# mapleCUx_large_050.net
KiCad netlist of a schematic drawn in EAGLE
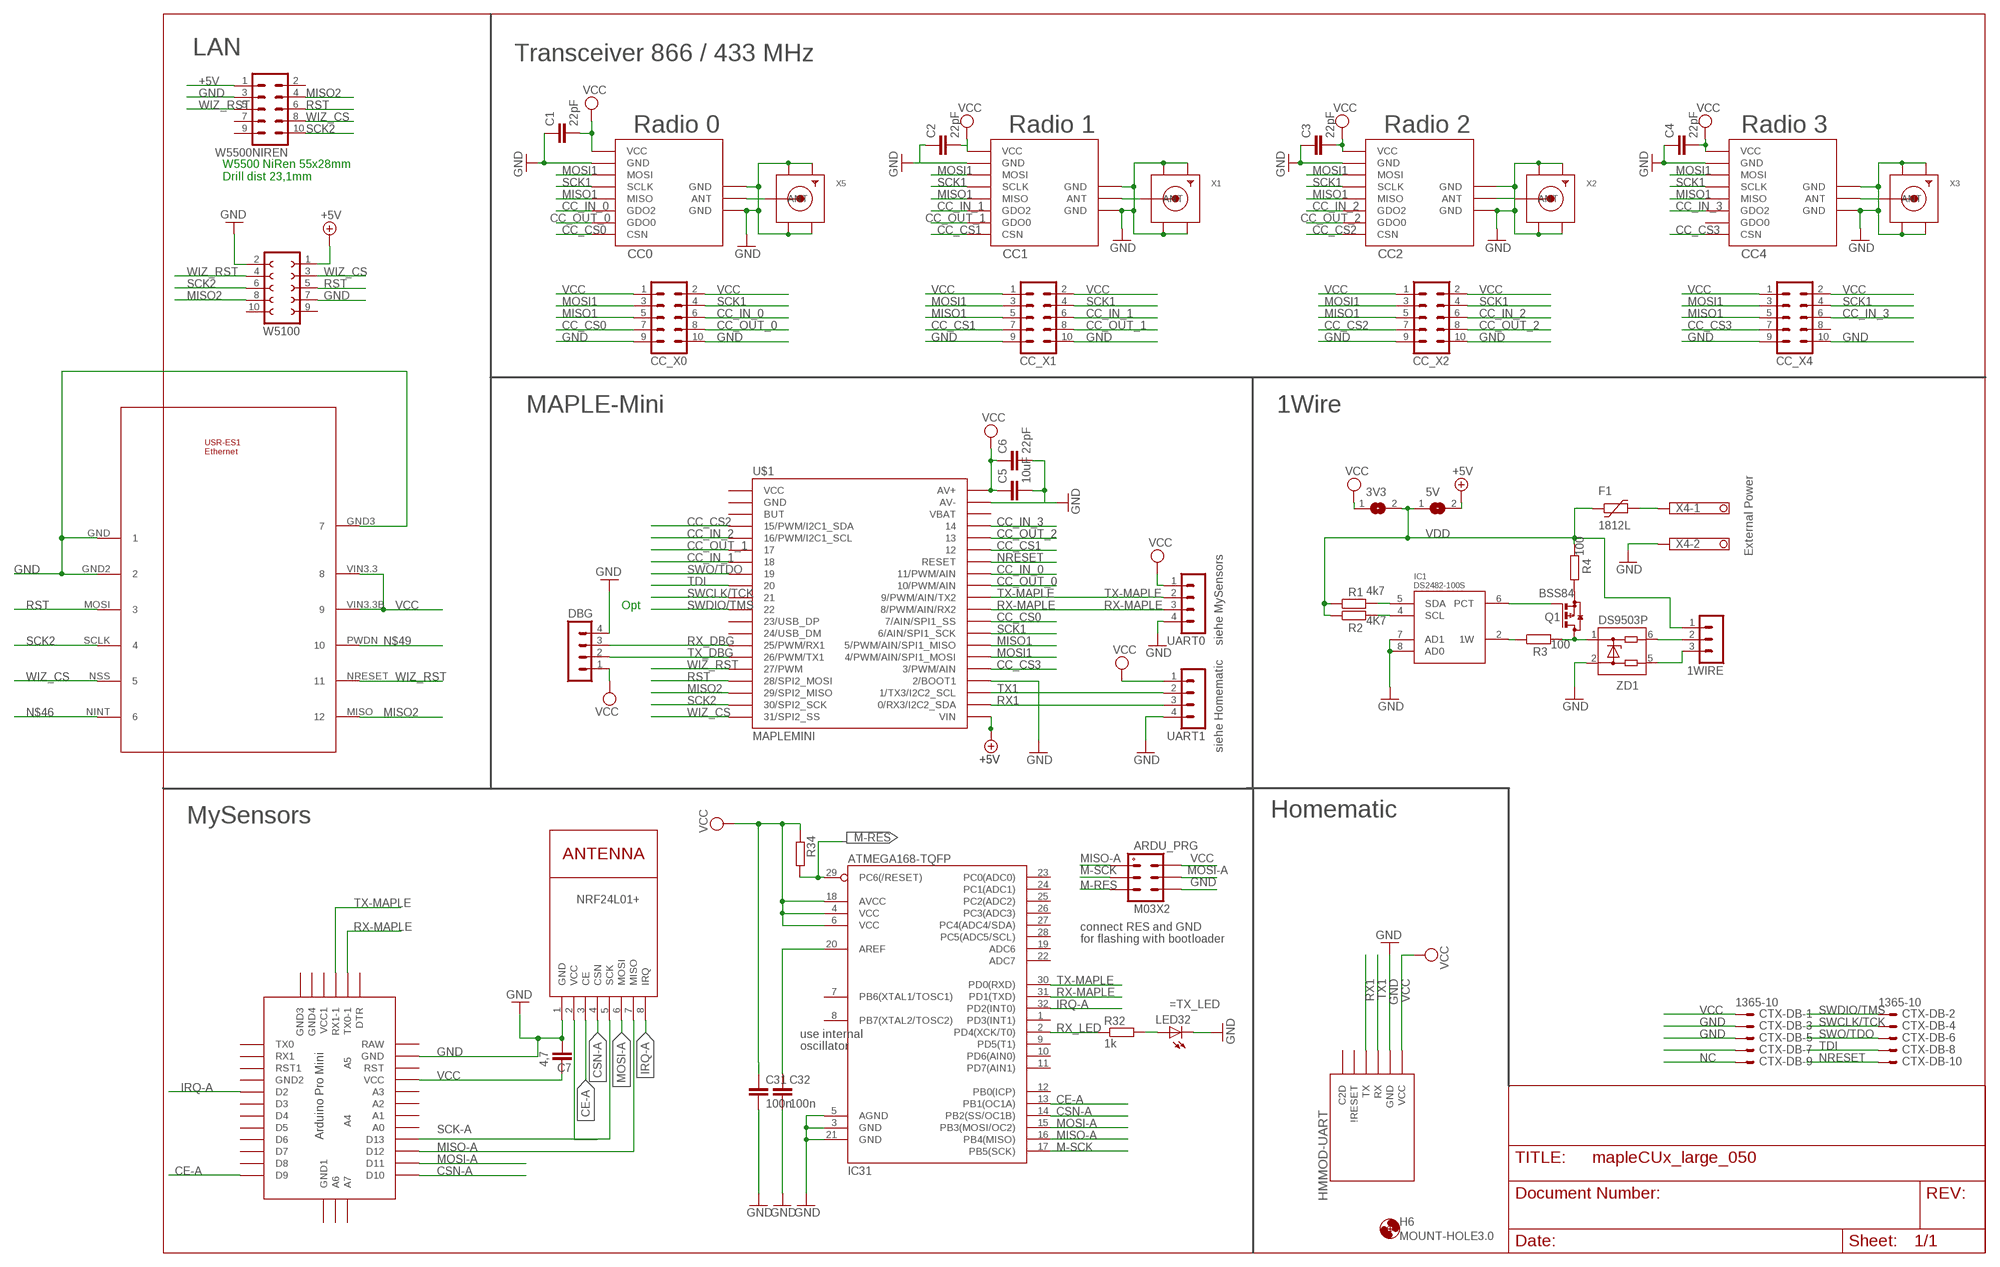
[diagram p0: schematic, sheet 1]

(export (version "E")
  (design (tool "Eeschema 10.0.6"))
  (components
    (comp (ref "1WIRE")
      (value "MA03-1")
      (footprint "eagle-import:MA03-1")
      (libsource (lib "eagle-import") (part "MA03-1"))
    )
    (comp (ref "3V3") (value "SJ") (footprint "eagle-import:SJ") (libsource (lib "eagle-import") (part "SJ")))
    (comp (ref "5V") (value "SJ") (footprint "eagle-import:SJ") (libsource (lib "eagle-import") (part "SJ")))
    (comp (ref "ARDU_PRG")
      (value "M03X2")
      (footprint "eagle-import:2X03-1.27MM_SMD")
      (libsource (lib "eagle-import") (part "M03X2"))
    )
    (comp (ref "C1")
      (value "22pF")
      (footprint "eagle-import:C0805")
      (libsource (lib "eagle-import") (part "C-EUC0805"))
    )
    (comp (ref "C2")
      (value "22pF")
      (footprint "eagle-import:C0805")
      (libsource (lib "eagle-import") (part "C-EUC0805"))
    )
    (comp (ref "C3")
      (value "22pF")
      (footprint "eagle-import:C0805")
      (libsource (lib "eagle-import") (part "C-EUC0805"))
    )
    (comp (ref "C4")
      (value "22pF")
      (footprint "eagle-import:C0805")
      (libsource (lib "eagle-import") (part "C-EUC0805"))
    )
    (comp (ref "C5")
      (value "10uF")
      (footprint "eagle-import:C1210")
      (libsource (lib "eagle-import") (part "C-EUC1210"))
    )
    (comp (ref "C6")
      (value "22pF")
      (footprint "eagle-import:C0805")
      (libsource (lib "eagle-import") (part "C-EUC0805"))
    )
    (comp (ref "C7")
      (value "4,7")
      (footprint "eagle-import:C1210")
      (libsource (lib "eagle-import") (part "C-EUC1210"))
    )
    (comp (ref "C31")
      (value "100n")
      (footprint "eagle-import:C0805")
      (libsource (lib "eagle-import") (part "C-EUC0805"))
    )
    (comp (ref "C32")
      (value "100n")
      (footprint "eagle-import:C0805")
      (libsource (lib "eagle-import") (part "C-EUC0805"))
    )
    (comp (ref "CC0")
      (value "CC1101_MODULE1SMD")
      (footprint "eagle-import:CC1101_MODULE1_SMD")
      (libsource (lib "eagle-import") (part "CC1101_MODULE1SMD"))
    )
    (comp (ref "CC1")
      (value "CC1101_MODULE1SMD")
      (footprint "eagle-import:CC1101_MODULE1_SMD")
      (libsource (lib "eagle-import") (part "CC1101_MODULE1SMD"))
    )
    (comp (ref "CC2")
      (value "CC1101_MODULE1SMD")
      (footprint "eagle-import:CC1101_MODULE1_SMD")
      (libsource (lib "eagle-import") (part "CC1101_MODULE1SMD"))
    )
    (comp (ref "CC4")
      (value "CC1101_MODULE1SMD")
      (footprint "eagle-import:CC1101_MODULE1_SMD")
      (libsource (lib "eagle-import") (part "CC1101_MODULE1SMD"))
    )
    (comp (ref "CC_X0")
      (value "MA05-2")
      (footprint "eagle-import:MA05-2")
      (libsource (lib "eagle-import") (part "MA05-2"))
    )
    (comp (ref "CC_X1")
      (value "MA05-2")
      (footprint "eagle-import:MA05-2")
      (libsource (lib "eagle-import") (part "MA05-2"))
    )
    (comp (ref "CC_X2")
      (value "MA05-2")
      (footprint "eagle-import:MA05-2")
      (libsource (lib "eagle-import") (part "MA05-2"))
    )
    (comp (ref "CC_X4")
      (value "MA05-2")
      (footprint "eagle-import:MA05-2")
      (libsource (lib "eagle-import") (part "MA05-2"))
    )
    (comp (ref "CTX-DB")
      (value "1365-10")
      (footprint "eagle-import:1365-10")
      (libsource (lib "eagle-import") (part "1365-10"))
    )
    (comp (ref "DBG")
      (value "MA04-1")
      (footprint "eagle-import:MA04-1")
      (libsource (lib "eagle-import") (part "MA04-1"))
    )
    (comp (ref "F1")
      (value "1812L")
      (footprint "eagle-import:1812L")
      (libsource (lib "eagle-import") (part "1812L"))
    )
    (comp (ref "H6")
      (value "MOUNT-HOLE3.0")
      (footprint "eagle-import:3,0")
      (libsource (lib "eagle-import") (part "MOUNT-HOLE3.0"))
    )
    (comp (ref "HMMOD-UART")
      (value "HM-MOD-UARTDIL")
      (footprint "eagle-import:HM-MOD-UART-DIL")
      (libsource (lib "eagle-import") (part "HM-MOD-UARTDIL"))
    )
    (comp (ref "IC1")
      (value "DS2482-100S")
      (footprint "eagle-import:SO08")
      (libsource (lib "eagle-import") (part "DS2482-100S"))
    )
    (comp (ref "IC31")
      (value "ATMEGA168-TQFP")
      (footprint "eagle-import:TQFP32-08")
      (libsource (lib "eagle-import") (part "ATMEGA168-TQFP"))
    )
    (comp (ref "LED32")
      (value "LEDCHIPLED_0805")
      (footprint "eagle-import:CHIPLED_0805")
      (libsource (lib "eagle-import") (part "LEDCHIPLED_0805"))
    )
    (comp (ref "NRF24L01+")
      (value "NRF24L01+")
      (footprint "eagle-import:WIRELESS-NRF24L01")
      (libsource (lib "eagle-import") (part "WIRELESS-NRF24L01"))
    )
    (comp (ref "Q1")
      (value "BSS84")
      (footprint "eagle-import:SOT23")
      (libsource (lib "eagle-import") (part "BSS84"))
    )
    (comp (ref "R1")
      (value "4k7")
      (footprint "eagle-import:R0805")
      (libsource (lib "eagle-import") (part "R-EU_R0805"))
    )
    (comp (ref "R2")
      (value "4K7")
      (footprint "eagle-import:R0805")
      (libsource (lib "eagle-import") (part "R-EU_R0805"))
    )
    (comp (ref "R3")
      (value "100")
      (footprint "eagle-import:R0805")
      (libsource (lib "eagle-import") (part "R-EU_R0805"))
    )
    (comp (ref "R4")
      (value "100")
      (footprint "eagle-import:R0805")
      (libsource (lib "eagle-import") (part "R-EU_R0805"))
    )
    (comp (ref "R32")
      (value "1k")
      (footprint "eagle-import:R0805")
      (libsource (lib "eagle-import") (part "R-EU_R0805"))
    )
    (comp (ref "R34")
      (value "R-EU_R0805")
      (footprint "eagle-import:R0805")
      (libsource (lib "eagle-import") (part "R-EU_R0805"))
    )
    (comp (ref "U$1")
      (value "MAPLEMINI")
      (footprint "eagle-import:20-DIP")
      (libsource (lib "eagle-import") (part "MAPLEMINI"))
    )
    (comp (ref "U$2")
      (value "ABK-PRO-MINI")
      (footprint "eagle-import:ABK-PRO-MINI")
      (libsource (lib "eagle-import") (part "ABK-PRO-MINI"))
    )
    (comp (ref "U$3")
      (value "USR-ES1")
      (footprint "eagle-import:USR-ES1")
      (libsource (lib "eagle-import") (part "USR-ES1"))
    )
    (comp (ref "UART0")
      (value "MA04-1")
      (footprint "eagle-import:MA04-1")
      (libsource (lib "eagle-import") (part "MA04-1"))
    )
    (comp (ref "UART1")
      (value "MA04-1")
      (footprint "eagle-import:MA04-1")
      (libsource (lib "eagle-import") (part "MA04-1"))
    )
    (comp (ref "W5100")
      (value "FE05-2")
      (footprint "eagle-import:FE05-2")
      (libsource (lib "eagle-import") (part "FE05-2"))
    )
    (comp (ref "W5500NIREN")
      (value "MA05-2")
      (footprint "eagle-import:MA05-2")
      (libsource (lib "eagle-import") (part "MA05-2"))
    )
    (comp (ref "X1")
      (value "SMACONNECTOR_EDGE_UFL")
      (footprint "eagle-import:SMA_EDGELAUNCH_UFL")
      (libsource (lib "eagle-import") (part "SMACONNECTOR_EDGE_UFL"))
    )
    (comp (ref "X2")
      (value "SMACONNECTOR_EDGE_UFL")
      (footprint "eagle-import:SMA_EDGELAUNCH_UFL")
      (libsource (lib "eagle-import") (part "SMACONNECTOR_EDGE_UFL"))
    )
    (comp (ref "X3")
      (value "SMACONNECTOR_EDGE_UFL")
      (footprint "eagle-import:SMA_EDGELAUNCH_UFL")
      (libsource (lib "eagle-import") (part "SMACONNECTOR_EDGE_UFL"))
    )
    (comp (ref "X4")
      (value "1751248")
      (footprint "eagle-import:1751248")
      (libsource (lib "eagle-import") (part "1751248"))
    )
    (comp (ref "X5")
      (value "SMACONNECTOR_EDGE_UFL")
      (footprint "eagle-import:SMA_EDGELAUNCH_UFL")
      (libsource (lib "eagle-import") (part "SMACONNECTOR_EDGE_UFL"))
    )
    (comp (ref "ZD1")
      (value "DS9503P")
      (footprint "eagle-import:TSOC6")
      (libsource (lib "eagle-import") (part "DS9503P"))
    )
  )
  (nets
    (net (code "1") (name "+5V") (class "Default")
      (node (ref "5V") (pin "2") (pinfunction "2_2") (pintype "passive"))
      (node (ref "U$1") (pin "21") (pinfunction "VIN_21") (pintype "bidirectional"))
      (node (ref "W5100") (pin "1") (pinfunction "1_1") (pintype "passive"))
      (node (ref "W5500NIREN") (pin "1") (pinfunction "1_1") (pintype "passive"))
    )
    (net (code "2") (name "/CC_CS0") (class "Default")
      (node (ref "CC0") (pin "CSN") (pinfunction "CSN_CSN") (pintype "bidirectional"))
      (node (ref "CC_X0") (pin "7") (pinfunction "7_7") (pintype "passive"))
      (node (ref "U$1") (pin "29") (pinfunction "7/AIN/SPI1_SS_29") (pintype "bidirectional"))
    )
    (net (code "3") (name "/CC_CS1") (class "Default")
      (node (ref "CC1") (pin "CSN") (pinfunction "CSN_CSN") (pintype "bidirectional"))
      (node (ref "CC_X1") (pin "7") (pinfunction "7_7") (pintype "passive"))
      (node (ref "U$1") (pin "35") (pinfunction "12_35") (pintype "bidirectional"))
    )
    (net (code "4") (name "/CC_CS2") (class "Default")
      (node (ref "CC2") (pin "CSN") (pinfunction "CSN_CSN") (pintype "bidirectional"))
      (node (ref "CC_X2") (pin "7") (pinfunction "7_7") (pintype "passive"))
      (node (ref "U$1") (pin "4") (pinfunction "15/PWM/I2C1_SDA_4") (pintype "bidirectional"))
    )
    (net (code "5") (name "/CC_CS3") (class "Default")
      (node (ref "CC4") (pin "CSN") (pinfunction "CSN_CSN") (pintype "bidirectional"))
      (node (ref "CC_X4") (pin "7") (pinfunction "7_7") (pintype "passive"))
      (node (ref "U$1") (pin "25") (pinfunction "3/PWM/AIN_25") (pintype "bidirectional"))
    )
    (net (code "6") (name "/CC_IN_0") (class "Default")
      (node (ref "CC0") (pin "GDO2") (pinfunction "GDO2_GDO2") (pintype "bidirectional"))
      (node (ref "CC_X0") (pin "6") (pinfunction "6_6") (pintype "passive"))
      (node (ref "U$1") (pin "33") (pinfunction "11/PWM/AIN_33") (pintype "bidirectional"))
    )
    (net (code "7") (name "/CC_IN_1") (class "Default")
      (node (ref "CC1") (pin "GDO2") (pinfunction "GDO2_GDO2") (pintype "bidirectional"))
      (node (ref "CC_X1") (pin "6") (pinfunction "6_6") (pintype "passive"))
      (node (ref "U$1") (pin "7") (pinfunction "18_7") (pintype "bidirectional"))
    )
    (net (code "8") (name "/CC_IN_2") (class "Default")
      (node (ref "CC2") (pin "GDO2") (pinfunction "GDO2_GDO2") (pintype "bidirectional"))
      (node (ref "CC_X2") (pin "6") (pinfunction "6_6") (pintype "passive"))
      (node (ref "U$1") (pin "5") (pinfunction "16/PWM/I2C1_SCL_5") (pintype "bidirectional"))
    )
    (net (code "9") (name "/CC_IN_3") (class "Default")
      (node (ref "CC4") (pin "GDO2") (pinfunction "GDO2_GDO2") (pintype "bidirectional"))
      (node (ref "CC_X4") (pin "6") (pinfunction "6_6") (pintype "passive"))
      (node (ref "U$1") (pin "37") (pinfunction "14_37") (pintype "bidirectional"))
    )
    (net (code "10") (name "/CC_OUT_0") (class "Default")
      (node (ref "CC0") (pin "GDO0") (pinfunction "GDO0_GDO0") (pintype "bidirectional"))
      (node (ref "CC_X0") (pin "8") (pinfunction "8_8") (pintype "passive"))
      (node (ref "U$1") (pin "32") (pinfunction "10/PWM/AIN_32") (pintype "bidirectional"))
    )
    (net (code "11") (name "/CC_OUT_1") (class "Default")
      (node (ref "CC1") (pin "GDO0") (pinfunction "GDO0_GDO0") (pintype "bidirectional"))
      (node (ref "CC_X1") (pin "8") (pinfunction "8_8") (pintype "passive"))
      (node (ref "U$1") (pin "6") (pinfunction "17_6") (pintype "bidirectional"))
    )
    (net (code "12") (name "/CC_OUT_2") (class "Default")
      (node (ref "CC2") (pin "GDO0") (pinfunction "GDO0_GDO0") (pintype "bidirectional"))
      (node (ref "CC_X2") (pin "8") (pinfunction "8_8") (pintype "passive"))
      (node (ref "U$1") (pin "36") (pinfunction "13_36") (pintype "bidirectional"))
    )
    (net (code "13") (name "/M-RES") (class "Default")
      (node (ref "ARDU_PRG") (pin "P$5") (pinfunction "5_P$5") (pintype "passive"))
      (node (ref "IC31") (pin "29") (pinfunction "PC6(/RESET)_29") (pintype "bidirectional"))
      (node (ref "R34") (pin "2") (pinfunction "2_2") (pintype "passive"))
    )
    (net (code "14") (name "/M-SCK") (class "Default")
      (node (ref "ARDU_PRG") (pin "P$3") (pinfunction "3_P$3") (pintype "passive"))
      (node (ref "IC31") (pin "17") (pinfunction "PB5(SCK)_17") (pintype "bidirectional"))
    )
    (net (code "15") (name "/MISO-A") (class "Default")
      (node (ref "ARDU_PRG") (pin "P$1") (pinfunction "1_P$1") (pintype "passive"))
      (node (ref "IC31") (pin "16") (pinfunction "PB4(MISO)_16") (pintype "bidirectional"))
      (node (ref "NRF24L01+") (pin "7") (pinfunction "MISO_7") (pintype "bidirectional"))
      (node (ref "U$2") (pin "D12") (pinfunction "D12_D12") (pintype "bidirectional"))
    )
    (net (code "16") (name "/MISO1") (class "Default")
      (node (ref "CC0") (pin "MISO") (pinfunction "MISO_MISO") (pintype "bidirectional"))
      (node (ref "CC1") (pin "MISO") (pinfunction "MISO_MISO") (pintype "bidirectional"))
      (node (ref "CC2") (pin "MISO") (pinfunction "MISO_MISO") (pintype "bidirectional"))
      (node (ref "CC4") (pin "MISO") (pinfunction "MISO_MISO") (pintype "bidirectional"))
      (node (ref "CC_X0") (pin "5") (pinfunction "5_5") (pintype "passive"))
      (node (ref "CC_X1") (pin "5") (pinfunction "5_5") (pintype "passive"))
      (node (ref "CC_X2") (pin "5") (pinfunction "5_5") (pintype "passive"))
      (node (ref "CC_X4") (pin "5") (pinfunction "5_5") (pintype "passive"))
      (node (ref "U$1") (pin "27") (pinfunction "5/PWM/AIN/SPI1_MISO_27") (pintype "bidirectional"))
    )
    (net (code "17") (name "/MISO2") (class "Default")
      (node (ref "U$1") (pin "18") (pinfunction "29/SPI2_MISO_18") (pintype "bidirectional"))
      (node (ref "U$3") (pin "MISO") (pinfunction "12_MISO") (pintype "bidirectional"))
      (node (ref "W5100") (pin "8") (pinfunction "8_8") (pintype "passive"))
      (node (ref "W5500NIREN") (pin "4") (pinfunction "4_4") (pintype "passive"))
    )
    (net (code "18") (name "/MOSI1") (class "Default")
      (node (ref "CC0") (pin "MOSI") (pinfunction "MOSI_MOSI") (pintype "bidirectional"))
      (node (ref "CC1") (pin "MOSI") (pinfunction "MOSI_MOSI") (pintype "bidirectional"))
      (node (ref "CC2") (pin "MOSI") (pinfunction "MOSI_MOSI") (pintype "bidirectional"))
      (node (ref "CC4") (pin "MOSI") (pinfunction "MOSI_MOSI") (pintype "bidirectional"))
      (node (ref "CC_X0") (pin "3") (pinfunction "3_3") (pintype "passive"))
      (node (ref "CC_X1") (pin "3") (pinfunction "3_3") (pintype "passive"))
      (node (ref "CC_X2") (pin "3") (pinfunction "3_3") (pintype "passive"))
      (node (ref "CC_X4") (pin "3") (pinfunction "3_3") (pintype "passive"))
      (node (ref "U$1") (pin "26") (pinfunction "4/PWM/AIN/SPI1_MOSI_26") (pintype "bidirectional"))
    )
    (net (code "19") (name "/N$46") (class "Default")
      (node (ref "U$3") (pin "NINT") (pinfunction "6_NINT") (pintype "bidirectional"))
    )
    (net (code "20") (name "/N$49") (class "Default")
      (node (ref "U$3") (pin "PWDN") (pinfunction "10_PWDN") (pintype "bidirectional"))
    )
    (net (code "21") (name "/NC") (class "Default")
      (node (ref "CTX-DB") (pin "9") (pinfunction "S_9") (pintype "passive"))
    )
    (net (code "22") (name "/NRESET") (class "Default")
      (node (ref "CTX-DB") (pin "10") (pinfunction "S_10") (pintype "passive"))
      (node (ref "U$1") (pin "34") (pinfunction "RESET_34") (pintype "bidirectional"))
    )
    (net (code "23") (name "/RST") (class "Default")
      (node (ref "U$1") (pin "17") (pinfunction "28/SPI2_MOSI_17") (pintype "bidirectional"))
      (node (ref "U$3") (pin "MOSI") (pinfunction "3_MOSI") (pintype "bidirectional"))
      (node (ref "W5100") (pin "5") (pinfunction "5_5") (pintype "passive"))
      (node (ref "W5500NIREN") (pin "6") (pinfunction "6_6") (pintype "passive"))
    )
    (net (code "24") (name "/RX-MAPLE") (class "Default")
      (node (ref "IC31") (pin "31") (pinfunction "PD1(TXD)_31") (pintype "bidirectional"))
      (node (ref "U$1") (pin "30") (pinfunction "8/PWM/AIN/RX2_30") (pintype "bidirectional"))
      (node (ref "U$2") (pin "TX0-1") (pinfunction "TX0-1_TX0-1") (pintype "bidirectional"))
      (node (ref "UART0") (pin "3") (pinfunction "3_3") (pintype "passive"))
    )
    (net (code "25") (name "/RX1") (class "Default")
      (node (ref "HMMOD-UART") (pin "5") (pinfunction "TX_5") (pintype "bidirectional"))
      (node (ref "U$1") (pin "22") (pinfunction "0/RX3/I2C2_SDA_22") (pintype "bidirectional"))
      (node (ref "UART1") (pin "3") (pinfunction "3_3") (pintype "passive"))
    )
    (net (code "26") (name "/RX_DBG") (class "Default")
      (node (ref "DBG") (pin "3") (pinfunction "3_3") (pintype "passive"))
      (node (ref "U$1") (pin "14") (pinfunction "25/PWM/RX1_14") (pintype "bidirectional"))
    )
    (net (code "27") (name "/RX_LED") (class "Default")
      (node (ref "IC31") (pin "2") (pinfunction "PD4(XCK/T0)_2") (pintype "bidirectional"))
      (node (ref "R32") (pin "1") (pinfunction "1_1") (pintype "passive"))
    )
    (net (code "28") (name "/SCK-A") (class "Default")
      (node (ref "NRF24L01+") (pin "5") (pinfunction "SCK_5") (pintype "bidirectional"))
      (node (ref "U$2") (pin "D13") (pinfunction "D13_D13") (pintype "bidirectional"))
    )
    (net (code "29") (name "/SCK1") (class "Default")
      (node (ref "CC0") (pin "SCLK") (pinfunction "SCLK_SCLK") (pintype "bidirectional"))
      (node (ref "CC1") (pin "SCLK") (pinfunction "SCLK_SCLK") (pintype "bidirectional"))
      (node (ref "CC2") (pin "SCLK") (pinfunction "SCLK_SCLK") (pintype "bidirectional"))
      (node (ref "CC4") (pin "SCLK") (pinfunction "SCLK_SCLK") (pintype "bidirectional"))
      (node (ref "CC_X0") (pin "4") (pinfunction "4_4") (pintype "passive"))
      (node (ref "CC_X1") (pin "4") (pinfunction "4_4") (pintype "passive"))
      (node (ref "CC_X2") (pin "4") (pinfunction "4_4") (pintype "passive"))
      (node (ref "CC_X4") (pin "4") (pinfunction "4_4") (pintype "passive"))
      (node (ref "U$1") (pin "28") (pinfunction "6/AIN/SPI1_SCK_28") (pintype "bidirectional"))
    )
    (net (code "30") (name "/SCK2") (class "Default")
      (node (ref "U$1") (pin "19") (pinfunction "30/SPI2_SCK_19") (pintype "bidirectional"))
      (node (ref "U$3") (pin "SCLK") (pinfunction "4_SCLK") (pintype "bidirectional"))
      (node (ref "W5100") (pin "6") (pinfunction "6_6") (pintype "passive"))
      (node (ref "W5500NIREN") (pin "10") (pinfunction "10_10") (pintype "passive"))
    )
    (net (code "31") (name "/SWCLK{slash}TCK") (class "Default")
      (node (ref "CTX-DB") (pin "4") (pinfunction "S_4") (pintype "passive"))
      (node (ref "U$1") (pin "10") (pinfunction "21_10") (pintype "bidirectional"))
    )
    (net (code "32") (name "/SWDIO{slash}TMS") (class "Default")
      (node (ref "CTX-DB") (pin "2") (pinfunction "S_2") (pintype "passive"))
      (node (ref "U$1") (pin "11") (pinfunction "22_11") (pintype "bidirectional"))
    )
    (net (code "33") (name "/SWO{slash}TDO") (class "Default")
      (node (ref "CTX-DB") (pin "6") (pinfunction "S_6") (pintype "passive"))
      (node (ref "U$1") (pin "8") (pinfunction "19_8") (pintype "bidirectional"))
    )
    (net (code "34") (name "/TDI") (class "Default")
      (node (ref "CTX-DB") (pin "8") (pinfunction "S_8") (pintype "passive"))
      (node (ref "U$1") (pin "9") (pinfunction "20_9") (pintype "bidirectional"))
    )
    (net (code "35") (name "/TX-MAPLE") (class "Default")
      (node (ref "IC31") (pin "30") (pinfunction "PD0(RXD)_30") (pintype "bidirectional"))
      (node (ref "U$1") (pin "31") (pinfunction "9/PWM/AIN/TX2_31") (pintype "bidirectional"))
      (node (ref "U$2") (pin "RX1-1") (pinfunction "RX1-1_RX1-1") (pintype "bidirectional"))
      (node (ref "UART0") (pin "2") (pinfunction "2_2") (pintype "passive"))
    )
    (net (code "36") (name "/TX1") (class "Default")
      (node (ref "HMMOD-UART") (pin "6") (pinfunction "RX_6") (pintype "bidirectional"))
      (node (ref "U$1") (pin "23") (pinfunction "1/TX3/I2C2_SCL_23") (pintype "bidirectional"))
      (node (ref "UART1") (pin "2") (pinfunction "2_2") (pintype "passive"))
    )
    (net (code "37") (name "/TX_DBG") (class "Default")
      (node (ref "DBG") (pin "2") (pinfunction "2_2") (pintype "passive"))
      (node (ref "U$1") (pin "15") (pinfunction "26/PWM/TX1_15") (pintype "bidirectional"))
    )
    (net (code "38") (name "/VDD") (class "Default")
      (node (ref "1WIRE") (pin "1") (pinfunction "1_1") (pintype "passive"))
      (node (ref "3V3") (pin "2") (pinfunction "2_2") (pintype "passive"))
      (node (ref "5V") (pin "1") (pinfunction "1_1") (pintype "passive"))
      (node (ref "F1") (pin "P$1") (pinfunction "1_P$1") (pintype "passive"))
      (node (ref "R1") (pin "1") (pinfunction "1_1") (pintype "passive"))
      (node (ref "R2") (pin "1") (pinfunction "1_1") (pintype "passive"))
      (node (ref "R4") (pin "2") (pinfunction "2_2") (pintype "passive"))
    )
    (net (code "39") (name "/WIZ_CS") (class "Default")
      (node (ref "U$1") (pin "20") (pinfunction "31/SPI2_SS_20") (pintype "bidirectional"))
      (node (ref "U$3") (pin "NSS") (pinfunction "5_NSS") (pintype "bidirectional"))
      (node (ref "W5100") (pin "3") (pinfunction "3_3") (pintype "passive"))
      (node (ref "W5500NIREN") (pin "8") (pinfunction "8_8") (pintype "passive"))
    )
    (net (code "40") (name "/WIZ_RST") (class "Default")
      (node (ref "U$1") (pin "16") (pinfunction "27/PWM_16") (pintype "bidirectional"))
      (node (ref "U$3") (pin "NRESET") (pinfunction "11_NRESET") (pintype "bidirectional"))
      (node (ref "W5100") (pin "4") (pinfunction "4_4") (pintype "passive"))
      (node (ref "W5500NIREN") (pin "5") (pinfunction "5_5") (pintype "passive"))
    )
    (net (code "41") (name "CE-A") (class "Default")
      (node (ref "IC31") (pin "13") (pinfunction "PB1(OC1A)_13") (pintype "bidirectional"))
      (node (ref "NRF24L01+") (pin "3") (pinfunction "CE_3") (pintype "bidirectional"))
      (node (ref "U$2") (pin "D9") (pinfunction "D9_D9") (pintype "bidirectional"))
    )
    (net (code "42") (name "CSN-A") (class "Default")
      (node (ref "IC31") (pin "14") (pinfunction "PB2(SS/OC1B)_14") (pintype "bidirectional"))
      (node (ref "NRF24L01+") (pin "4") (pinfunction "CSN_4") (pintype "bidirectional"))
      (node (ref "U$2") (pin "D10") (pinfunction "D10_D10") (pintype "bidirectional"))
    )
    (net (code "43") (name "GND") (class "Default")
      (node (ref "ARDU_PRG") (pin "P$6") (pinfunction "6_P$6") (pintype "passive"))
      (node (ref "C1") (pin "1") (pinfunction "1_1") (pintype "passive"))
      (node (ref "C2") (pin "1") (pinfunction "1_1") (pintype "passive"))
      (node (ref "C3") (pin "1") (pinfunction "1_1") (pintype "passive"))
      (node (ref "C31") (pin "2") (pinfunction "2_2") (pintype "passive"))
      (node (ref "C32") (pin "2") (pinfunction "2_2") (pintype "passive"))
      (node (ref "C4") (pin "1") (pinfunction "1_1") (pintype "passive"))
      (node (ref "C5") (pin "2") (pinfunction "2_2") (pintype "passive"))
      (node (ref "C6") (pin "2") (pinfunction "2_2") (pintype "passive"))
      (node (ref "C7") (pin "1") (pinfunction "1_1") (pintype "passive"))
      (node (ref "CC0") (pin "GND@0") (pinfunction "GND_GND@0") (pintype "power_in"))
      (node (ref "CC0") (pin "GND@1") (pinfunction "GND_GND@1") (pintype "power_in"))
      (node (ref "CC0") (pin "GND@2") (pinfunction "GND_GND@2") (pintype "power_in"))
      (node (ref "CC1") (pin "GND@0") (pinfunction "GND_GND@0") (pintype "power_in"))
      (node (ref "CC1") (pin "GND@1") (pinfunction "GND_GND@1") (pintype "power_in"))
      (node (ref "CC1") (pin "GND@2") (pinfunction "GND_GND@2") (pintype "power_in"))
      (node (ref "CC2") (pin "GND@0") (pinfunction "GND_GND@0") (pintype "power_in"))
      (node (ref "CC2") (pin "GND@1") (pinfunction "GND_GND@1") (pintype "power_in"))
      (node (ref "CC2") (pin "GND@2") (pinfunction "GND_GND@2") (pintype "power_in"))
      (node (ref "CC4") (pin "GND@0") (pinfunction "GND_GND@0") (pintype "power_in"))
      (node (ref "CC4") (pin "GND@1") (pinfunction "GND_GND@1") (pintype "power_in"))
      (node (ref "CC4") (pin "GND@2") (pinfunction "GND_GND@2") (pintype "power_in"))
      (node (ref "CC_X0") (pin "10") (pinfunction "10_10") (pintype "passive"))
      (node (ref "CC_X0") (pin "9") (pinfunction "9_9") (pintype "passive"))
      (node (ref "CC_X1") (pin "10") (pinfunction "10_10") (pintype "passive"))
      (node (ref "CC_X1") (pin "9") (pinfunction "9_9") (pintype "passive"))
      (node (ref "CC_X2") (pin "10") (pinfunction "10_10") (pintype "passive"))
      (node (ref "CC_X2") (pin "9") (pinfunction "9_9") (pintype "passive"))
      (node (ref "CC_X4") (pin "10") (pinfunction "10_10") (pintype "passive"))
      (node (ref "CC_X4") (pin "9") (pinfunction "9_9") (pintype "passive"))
      (node (ref "CTX-DB") (pin "3") (pinfunction "S_3") (pintype "passive"))
      (node (ref "CTX-DB") (pin "5") (pinfunction "S_5") (pintype "passive"))
      (node (ref "DBG") (pin "4") (pinfunction "4_4") (pintype "passive"))
      (node (ref "HMMOD-UART") (pin "2") (pinfunction "GND_2") (pintype "power_in"))
      (node (ref "IC1") (pin "7") (pinfunction "AD1_7") (pintype "input"))
      (node (ref "IC1") (pin "8") (pinfunction "AD0_8") (pintype "input"))
      (node (ref "IC31") (pin "21") (pinfunction "GND_21") (pintype "bidirectional"))
      (node (ref "IC31") (pin "3") (pinfunction "GND_3") (pintype "bidirectional"))
      (node (ref "IC31") (pin "5") (pinfunction "AGND_5") (pintype "bidirectional"))
      (node (ref "LED32") (pin "C") (pinfunction "C_C") (pintype "passive"))
      (node (ref "NRF24L01+") (pin "1") (pinfunction "GND_1") (pintype "power_in"))
      (node (ref "U$1") (pin "24") (pinfunction "2/BOOT1_24") (pintype "bidirectional"))
      (node (ref "U$1") (pin "39") (pinfunction "AV-_39") (pintype "bidirectional"))
      (node (ref "U$2") (pin "GND") (pinfunction "GND_GND") (pintype "bidirectional"))
      (node (ref "U$3") (pin "GND") (pinfunction "1_GND") (pintype "power_in"))
      (node (ref "U$3") (pin "GND2") (pinfunction "2_GND2") (pintype "power_in"))
      (node (ref "U$3") (pin "GND3") (pinfunction "7_GND3") (pintype "power_in"))
      (node (ref "UART0") (pin "4") (pinfunction "4_4") (pintype "passive"))
      (node (ref "UART1") (pin "4") (pinfunction "4_4") (pintype "passive"))
      (node (ref "W5100") (pin "2") (pinfunction "2_2") (pintype "passive"))
      (node (ref "W5100") (pin "7") (pinfunction "7_7") (pintype "passive"))
      (node (ref "W5500NIREN") (pin "3") (pinfunction "3_3") (pintype "passive"))
      (node (ref "X1") (pin "GND@1") (pinfunction "GND1_GND@1") (pintype "power_in"))
      (node (ref "X1") (pin "GND@2") (pinfunction "GND2_GND@2") (pintype "power_in"))
      (node (ref "X1") (pin "GND@3") (pinfunction "GND3_GND@3") (pintype "power_in"))
      (node (ref "X1") (pin "GND@4") (pinfunction "GND4_GND@4") (pintype "power_in"))
      (node (ref "X2") (pin "GND@1") (pinfunction "GND1_GND@1") (pintype "power_in"))
      (node (ref "X2") (pin "GND@2") (pinfunction "GND2_GND@2") (pintype "power_in"))
      (node (ref "X2") (pin "GND@3") (pinfunction "GND3_GND@3") (pintype "power_in"))
      (node (ref "X2") (pin "GND@4") (pinfunction "GND4_GND@4") (pintype "power_in"))
      (node (ref "X3") (pin "GND@1") (pinfunction "GND1_GND@1") (pintype "power_in"))
      (node (ref "X3") (pin "GND@2") (pinfunction "GND2_GND@2") (pintype "power_in"))
      (node (ref "X3") (pin "GND@3") (pinfunction "GND3_GND@3") (pintype "power_in"))
      (node (ref "X3") (pin "GND@4") (pinfunction "GND4_GND@4") (pintype "power_in"))
      (node (ref "X4") (pin "2") (pinfunction "K_2") (pintype "passive"))
      (node (ref "X5") (pin "GND@1") (pinfunction "GND1_GND@1") (pintype "power_in"))
      (node (ref "X5") (pin "GND@2") (pinfunction "GND2_GND@2") (pintype "power_in"))
      (node (ref "X5") (pin "GND@3") (pinfunction "GND3_GND@3") (pintype "power_in"))
      (node (ref "X5") (pin "GND@4") (pinfunction "GND4_GND@4") (pintype "power_in"))
      (node (ref "ZD1") (pin "2") (pinfunction "P$2_2") (pintype "passive"))
    )
    (net (code "44") (name "IRQ-A") (class "Default")
      (node (ref "IC31") (pin "32") (pinfunction "PD2(INT0)_32") (pintype "bidirectional"))
      (node (ref "NRF24L01+") (pin "8") (pinfunction "IRQ_8") (pintype "bidirectional"))
      (node (ref "U$2") (pin "D2") (pinfunction "D2_D2") (pintype "bidirectional"))
    )
    (net (code "45") (name "MOSI-A") (class "Default")
      (node (ref "ARDU_PRG") (pin "P$4") (pinfunction "4_P$4") (pintype "passive"))
      (node (ref "IC31") (pin "15") (pinfunction "PB3(MOSI/OC2)_15") (pintype "bidirectional"))
      (node (ref "NRF24L01+") (pin "6") (pinfunction "MOSI_6") (pintype "bidirectional"))
      (node (ref "U$2") (pin "D11") (pinfunction "D11_D11") (pintype "bidirectional"))
    )
    (net (code "46") (name "Net-(F1-2)") (class "Default")
      (node (ref "F1") (pin "P$2") (pinfunction "2_P$2") (pintype "passive"))
      (node (ref "X4") (pin "1") (pinfunction "K_1") (pintype "passive"))
    )
    (net (code "47") (name "Net-(IC1A-1W)") (class "Default")
      (node (ref "IC1") (pin "2") (pinfunction "1W_2") (pintype "open_collector"))
      (node (ref "R3") (pin "1") (pinfunction "1_1") (pintype "passive"))
    )
    (net (code "48") (name "Net-(IC1A-PCT)") (class "Default")
      (node (ref "IC1") (pin "6") (pinfunction "PCT_6") (pintype "output"))
      (node (ref "Q1") (pin "1") (pinfunction "G_1") (pintype "passive"))
    )
    (net (code "49") (name "Net-(IC1A-SCL)") (class "Default")
      (node (ref "IC1") (pin "4") (pinfunction "SCL_4") (pintype "input"))
      (node (ref "R2") (pin "2") (pinfunction "2_2") (pintype "passive"))
    )
    (net (code "50") (name "Net-(IC1A-SDA)") (class "Default")
      (node (ref "IC1") (pin "5") (pinfunction "SDA_5") (pintype "bidirectional"))
      (node (ref "R1") (pin "2") (pinfunction "2_2") (pintype "passive"))
    )
    (net (code "51") (name "Net-(IC31-AREF)") (class "Default")
      (node (ref "C32") (pin "1") (pinfunction "1_1") (pintype "passive"))
      (node (ref "IC31") (pin "20") (pinfunction "AREF_20") (pintype "bidirectional"))
    )
    (net (code "52") (name "Net-(LED32-PadA)") (class "Default")
      (node (ref "LED32") (pin "A") (pinfunction "A_A") (pintype "passive"))
      (node (ref "R32") (pin "2") (pinfunction "2_2") (pintype "passive"))
    )
    (net (code "53") (name "Net-(Q1-D)") (class "Default")
      (node (ref "Q1") (pin "3") (pinfunction "D_3") (pintype "passive"))
      (node (ref "R3") (pin "2") (pinfunction "2_2") (pintype "passive"))
      (node (ref "ZD1") (pin "1") (pinfunction "P$1_1") (pintype "passive"))
    )
    (net (code "54") (name "Net-(Q1-S)") (class "Default")
      (node (ref "Q1") (pin "2") (pinfunction "S_2") (pintype "passive"))
      (node (ref "R4") (pin "1") (pinfunction "1_1") (pintype "passive"))
    )
    (net (code "55") (name "Net-(X1-ANT)") (class "Default")
      (node (ref "CC1") (pin "ANT") (pinfunction "ANT_ANT") (pintype "output"))
      (node (ref "X1") (pin "P") (pinfunction "ANT_P") (pintype "bidirectional"))
    )
    (net (code "56") (name "Net-(X2-ANT)") (class "Default")
      (node (ref "CC2") (pin "ANT") (pinfunction "ANT_ANT") (pintype "output"))
      (node (ref "X2") (pin "P") (pinfunction "ANT_P") (pintype "bidirectional"))
    )
    (net (code "57") (name "Net-(X3-ANT)") (class "Default")
      (node (ref "CC4") (pin "ANT") (pinfunction "ANT_ANT") (pintype "output"))
      (node (ref "X3") (pin "P") (pinfunction "ANT_P") (pintype "bidirectional"))
    )
    (net (code "58") (name "Net-(X5-ANT)") (class "Default")
      (node (ref "CC0") (pin "ANT") (pinfunction "ANT_ANT") (pintype "output"))
      (node (ref "X5") (pin "P") (pinfunction "ANT_P") (pintype "bidirectional"))
    )
    (net (code "59") (name "Net-(ZD1-P$3)") (class "Default")
      (node (ref "1WIRE") (pin "3") (pinfunction "3_3") (pintype "passive"))
      (node (ref "ZD1") (pin "5") (pinfunction "P$3_5") (pintype "passive"))
    )
    (net (code "60") (name "Net-(ZD1-P$4)") (class "Default")
      (node (ref "1WIRE") (pin "2") (pinfunction "2_2") (pintype "passive"))
      (node (ref "ZD1") (pin "6") (pinfunction "P$4_6") (pintype "passive"))
    )
    (net (code "61") (name "VCC") (class "Default")
      (node (ref "3V3") (pin "1") (pinfunction "1_1") (pintype "passive"))
      (node (ref "ARDU_PRG") (pin "P$2") (pinfunction "2_P$2") (pintype "passive"))
      (node (ref "C1") (pin "2") (pinfunction "2_2") (pintype "passive"))
      (node (ref "C2") (pin "2") (pinfunction "2_2") (pintype "passive"))
      (node (ref "C3") (pin "2") (pinfunction "2_2") (pintype "passive"))
      (node (ref "C31") (pin "1") (pinfunction "1_1") (pintype "passive"))
      (node (ref "C4") (pin "2") (pinfunction "2_2") (pintype "passive"))
      (node (ref "C5") (pin "1") (pinfunction "1_1") (pintype "passive"))
      (node (ref "C6") (pin "1") (pinfunction "1_1") (pintype "passive"))
      (node (ref "C7") (pin "2") (pinfunction "2_2") (pintype "passive"))
      (node (ref "CC0") (pin "VCC") (pinfunction "VCC_VCC") (pintype "power_in"))
      (node (ref "CC1") (pin "VCC") (pinfunction "VCC_VCC") (pintype "power_in"))
      (node (ref "CC2") (pin "VCC") (pinfunction "VCC_VCC") (pintype "power_in"))
      (node (ref "CC4") (pin "VCC") (pinfunction "VCC_VCC") (pintype "power_in"))
      (node (ref "CC_X0") (pin "1") (pinfunction "1_1") (pintype "passive"))
      (node (ref "CC_X0") (pin "2") (pinfunction "2_2") (pintype "passive"))
      (node (ref "CC_X1") (pin "1") (pinfunction "1_1") (pintype "passive"))
      (node (ref "CC_X1") (pin "2") (pinfunction "2_2") (pintype "passive"))
      (node (ref "CC_X2") (pin "1") (pinfunction "1_1") (pintype "passive"))
      (node (ref "CC_X2") (pin "2") (pinfunction "2_2") (pintype "passive"))
      (node (ref "CC_X4") (pin "1") (pinfunction "1_1") (pintype "passive"))
      (node (ref "CC_X4") (pin "2") (pinfunction "2_2") (pintype "passive"))
      (node (ref "CTX-DB") (pin "1") (pinfunction "S_1") (pintype "passive"))
      (node (ref "DBG") (pin "1") (pinfunction "1_1") (pintype "passive"))
      (node (ref "HMMOD-UART") (pin "1") (pinfunction "VCC_1") (pintype "power_in"))
      (node (ref "IC31") (pin "18") (pinfunction "AVCC_18") (pintype "bidirectional"))
      (node (ref "IC31") (pin "4") (pinfunction "VCC_4") (pintype "bidirectional"))
      (node (ref "IC31") (pin "6") (pinfunction "VCC_6") (pintype "bidirectional"))
      (node (ref "NRF24L01+") (pin "2") (pinfunction "VCC_2") (pintype "power_in"))
      (node (ref "R34") (pin "1") (pinfunction "1_1") (pintype "passive"))
      (node (ref "U$1") (pin "40") (pinfunction "AV+_40") (pintype "bidirectional"))
      (node (ref "U$2") (pin "VCC") (pinfunction "VCC_VCC") (pintype "bidirectional"))
      (node (ref "U$3") (pin "VIN3.3") (pinfunction "8_VIN3.3") (pintype "power_in"))
      (node (ref "U$3") (pin "VIN3.3B") (pinfunction "9_VIN3.3B") (pintype "bidirectional"))
      (node (ref "UART0") (pin "1") (pinfunction "1_1") (pintype "passive"))
      (node (ref "UART1") (pin "1") (pinfunction "1_1") (pintype "passive"))
    )
    (net (code "62") (name "unconnected-(CC4-PadGDO0)") (class "Default")
      (node (ref "CC4") (pin "GDO0") (pinfunction "GDO0_GDO0") (pintype "bidirectional"))
    )
    (net (code "63") (name "unconnected-(CC_X4-Pad8)") (class "Default")
      (node (ref "CC_X4") (pin "8") (pinfunction "8_8") (pintype "passive"))
    )
    (net (code "64") (name "unconnected-(CTX-DBH-S-Pad7)") (class "Default")
      (node (ref "CTX-DB") (pin "7") (pinfunction "S_7") (pintype "passive"))
    )
    (net (code "65") (name "unconnected-(HMMOD-UART-C2D-Pad3)") (class "Default")
      (node (ref "HMMOD-UART") (pin "3") (pinfunction "C2D_3") (pintype "bidirectional"))
    )
    (net (code "66") (name "unconnected-(HMMOD-UART-\\~{RESET}-Pad4)") (class "Default")
      (node (ref "HMMOD-UART") (pin "4") (pinfunction "\\~{RESET}_4") (pintype "bidirectional"))
    )
    (net (code "67") (name "unconnected-(IC31-ADC6-Pad19)") (class "Default")
      (node (ref "IC31") (pin "19") (pinfunction "ADC6_19") (pintype "bidirectional"))
    )
    (net (code "68") (name "unconnected-(IC31-ADC7-Pad22)") (class "Default")
      (node (ref "IC31") (pin "22") (pinfunction "ADC7_22") (pintype "bidirectional"))
    )
    (net (code "69") (name "unconnected-(IC31-PB0(ICP)-Pad12)") (class "Default")
      (node (ref "IC31") (pin "12") (pinfunction "PB0(ICP)_12") (pintype "bidirectional"))
    )
    (net (code "70") (name "unconnected-(IC31-PB6(XTAL1{slash}TOSC1)-Pad7)") (class "Default")
      (node (ref "IC31") (pin "7") (pinfunction "PB6(XTAL1/TOSC1)_7") (pintype "bidirectional"))
    )
    (net (code "71") (name "unconnected-(IC31-PB7(XTAL2{slash}TOSC2)-Pad8)") (class "Default")
      (node (ref "IC31") (pin "8") (pinfunction "PB7(XTAL2/TOSC2)_8") (pintype "bidirectional"))
    )
    (net (code "72") (name "unconnected-(IC31-PC0(ADC0)-Pad23)") (class "Default")
      (node (ref "IC31") (pin "23") (pinfunction "PC0(ADC0)_23") (pintype "bidirectional"))
    )
    (net (code "73") (name "unconnected-(IC31-PC1(ADC1)-Pad24)") (class "Default")
      (node (ref "IC31") (pin "24") (pinfunction "PC1(ADC1)_24") (pintype "bidirectional"))
    )
    (net (code "74") (name "unconnected-(IC31-PC2(ADC2)-Pad25)") (class "Default")
      (node (ref "IC31") (pin "25") (pinfunction "PC2(ADC2)_25") (pintype "bidirectional"))
    )
    (net (code "75") (name "unconnected-(IC31-PC3(ADC3)-Pad26)") (class "Default")
      (node (ref "IC31") (pin "26") (pinfunction "PC3(ADC3)_26") (pintype "bidirectional"))
    )
    (net (code "76") (name "unconnected-(IC31-PC4(ADC4{slash}SDA)-Pad27)") (class "Default")
      (node (ref "IC31") (pin "27") (pinfunction "PC4(ADC4/SDA)_27") (pintype "bidirectional"))
    )
    (net (code "77") (name "unconnected-(IC31-PC5(ADC5{slash}SCL)-Pad28)") (class "Default")
      (node (ref "IC31") (pin "28") (pinfunction "PC5(ADC5/SCL)_28") (pintype "bidirectional"))
    )
    (net (code "78") (name "unconnected-(IC31-PD3(INT1)-Pad1)") (class "Default")
      (node (ref "IC31") (pin "1") (pinfunction "PD3(INT1)_1") (pintype "bidirectional"))
    )
    (net (code "79") (name "unconnected-(IC31-PD5(T1)-Pad9)") (class "Default")
      (node (ref "IC31") (pin "9") (pinfunction "PD5(T1)_9") (pintype "bidirectional"))
    )
    (net (code "80") (name "unconnected-(IC31-PD6(AIN0)-Pad10)") (class "Default")
      (node (ref "IC31") (pin "10") (pinfunction "PD6(AIN0)_10") (pintype "bidirectional"))
    )
    (net (code "81") (name "unconnected-(IC31-PD7(AIN1)-Pad11)") (class "Default")
      (node (ref "IC31") (pin "11") (pinfunction "PD7(AIN1)_11") (pintype "bidirectional"))
    )
    (net (code "82") (name "unconnected-(U$1-23{slash}USB_DP-Pad12)") (class "Default")
      (node (ref "U$1") (pin "12") (pinfunction "23/USB_DP_12") (pintype "bidirectional"))
    )
    (net (code "83") (name "unconnected-(U$1-24{slash}USB_DM-Pad13)") (class "Default")
      (node (ref "U$1") (pin "13") (pinfunction "24/USB_DM_13") (pintype "bidirectional"))
    )
    (net (code "84") (name "unconnected-(U$1-BUT-Pad3)") (class "Default")
      (node (ref "U$1") (pin "3") (pinfunction "BUT_3") (pintype "bidirectional"))
    )
    (net (code "85") (name "unconnected-(U$1-GND-Pad2)") (class "Default")
      (node (ref "U$1") (pin "2") (pinfunction "GND_2") (pintype "bidirectional"))
    )
    (net (code "86") (name "unconnected-(U$1-VBAT-Pad38)") (class "Default")
      (node (ref "U$1") (pin "38") (pinfunction "VBAT_38") (pintype "bidirectional"))
    )
    (net (code "87") (name "unconnected-(U$1-VCC-Pad1)") (class "Default")
      (node (ref "U$1") (pin "1") (pinfunction "VCC_1") (pintype "bidirectional"))
    )
    (net (code "88") (name "unconnected-(U$2-GND1-PadGND4)") (class "Default")
      (node (ref "U$2") (pin "GND4") (pinfunction "GND1_GND4") (pintype "bidirectional"))
    )
    (net (code "89") (name "unconnected-(U$2-GND2-PadGND1)") (class "Default")
      (node (ref "U$2") (pin "GND1") (pinfunction "GND2_GND1") (pintype "bidirectional"))
    )
    (net (code "90") (name "unconnected-(U$2-GND3-PadGND2)") (class "Default")
      (node (ref "U$2") (pin "GND2") (pinfunction "GND3_GND2") (pintype "bidirectional"))
    )
    (net (code "91") (name "unconnected-(U$2-GND4-PadGND3)") (class "Default")
      (node (ref "U$2") (pin "GND3") (pinfunction "GND4_GND3") (pintype "bidirectional"))
    )
    (net (code "92") (name "unconnected-(U$2-PadA0)") (class "Default")
      (node (ref "U$2") (pin "A0") (pinfunction "A0_A0") (pintype "bidirectional"))
    )
    (net (code "93") (name "unconnected-(U$2-PadA1)") (class "Default")
      (node (ref "U$2") (pin "A1") (pinfunction "A1_A1") (pintype "bidirectional"))
    )
    (net (code "94") (name "unconnected-(U$2-PadA2)") (class "Default")
      (node (ref "U$2") (pin "A2") (pinfunction "A2_A2") (pintype "bidirectional"))
    )
    (net (code "95") (name "unconnected-(U$2-PadA3)") (class "Default")
      (node (ref "U$2") (pin "A3") (pinfunction "A3_A3") (pintype "bidirectional"))
    )
    (net (code "96") (name "unconnected-(U$2-PadA4)") (class "Default")
      (node (ref "U$2") (pin "A4") (pinfunction "A4_A4") (pintype "bidirectional"))
    )
    (net (code "97") (name "unconnected-(U$2-PadA5)") (class "Default")
      (node (ref "U$2") (pin "A5") (pinfunction "A5_A5") (pintype "bidirectional"))
    )
    (net (code "98") (name "unconnected-(U$2-PadA6)") (class "Default")
      (node (ref "U$2") (pin "A6") (pinfunction "A6_A6") (pintype "bidirectional"))
    )
    (net (code "99") (name "unconnected-(U$2-PadA7)") (class "Default")
      (node (ref "U$2") (pin "A7") (pinfunction "A7_A7") (pintype "bidirectional"))
    )
    (net (code "100") (name "unconnected-(U$2-PadD3)") (class "Default")
      (node (ref "U$2") (pin "D3") (pinfunction "D3_D3") (pintype "bidirectional"))
    )
    (net (code "101") (name "unconnected-(U$2-PadD4)") (class "Default")
      (node (ref "U$2") (pin "D4") (pinfunction "D4_D4") (pintype "bidirectional"))
    )
    (net (code "102") (name "unconnected-(U$2-PadD5)") (class "Default")
      (node (ref "U$2") (pin "D5") (pinfunction "D5_D5") (pintype "bidirectional"))
    )
    (net (code "103") (name "unconnected-(U$2-PadD6)") (class "Default")
      (node (ref "U$2") (pin "D6") (pinfunction "D6_D6") (pintype "bidirectional"))
    )
    (net (code "104") (name "unconnected-(U$2-PadD7)") (class "Default")
      (node (ref "U$2") (pin "D7") (pinfunction "D7_D7") (pintype "bidirectional"))
    )
    (net (code "105") (name "unconnected-(U$2-PadD8)") (class "Default")
      (node (ref "U$2") (pin "D8") (pinfunction "D8_D8") (pintype "bidirectional"))
    )
    (net (code "106") (name "unconnected-(U$2-PadDTR)") (class "Default")
      (node (ref "U$2") (pin "DTR") (pinfunction "DTR_DTR") (pintype "bidirectional"))
    )
    (net (code "107") (name "unconnected-(U$2-PadRAW)") (class "Default")
      (node (ref "U$2") (pin "RAW") (pinfunction "RAW_RAW") (pintype "bidirectional"))
    )
    (net (code "108") (name "unconnected-(U$2-PadRST)") (class "Default")
      (node (ref "U$2") (pin "RST") (pinfunction "RST_RST") (pintype "bidirectional"))
    )
    (net (code "109") (name "unconnected-(U$2-PadRST1)") (class "Default")
      (node (ref "U$2") (pin "RST1") (pinfunction "RST1_RST1") (pintype "bidirectional"))
    )
    (net (code "110") (name "unconnected-(U$2-PadRX1)") (class "Default")
      (node (ref "U$2") (pin "RX1") (pinfunction "RX1_RX1") (pintype "bidirectional"))
    )
    (net (code "111") (name "unconnected-(U$2-PadTX0)") (class "Default")
      (node (ref "U$2") (pin "TX0") (pinfunction "TX0_TX0") (pintype "bidirectional"))
    )
    (net (code "112") (name "unconnected-(U$2-PadVCC1)") (class "Default")
      (node (ref "U$2") (pin "VCC1") (pinfunction "VCC1_VCC1") (pintype "bidirectional"))
    )
    (net (code "113") (name "unconnected-(W5100-Pad9)") (class "Default")
      (node (ref "W5100") (pin "9") (pinfunction "9_9") (pintype "passive"))
    )
    (net (code "114") (name "unconnected-(W5100-Pad10)") (class "Default")
      (node (ref "W5100") (pin "10") (pinfunction "10_10") (pintype "passive"))
    )
    (net (code "115") (name "unconnected-(W5500NIREN-Pad2)") (class "Default")
      (node (ref "W5500NIREN") (pin "2") (pinfunction "2_2") (pintype "passive"))
    )
    (net (code "116") (name "unconnected-(W5500NIREN-Pad7)") (class "Default")
      (node (ref "W5500NIREN") (pin "7") (pinfunction "7_7") (pintype "passive"))
    )
    (net (code "117") (name "unconnected-(W5500NIREN-Pad9)") (class "Default")
      (node (ref "W5500NIREN") (pin "9") (pinfunction "9_9") (pintype "passive"))
    )
  )
)
